# Smersh2.net
KiCad netlist of a schematic drawn in EAGLE
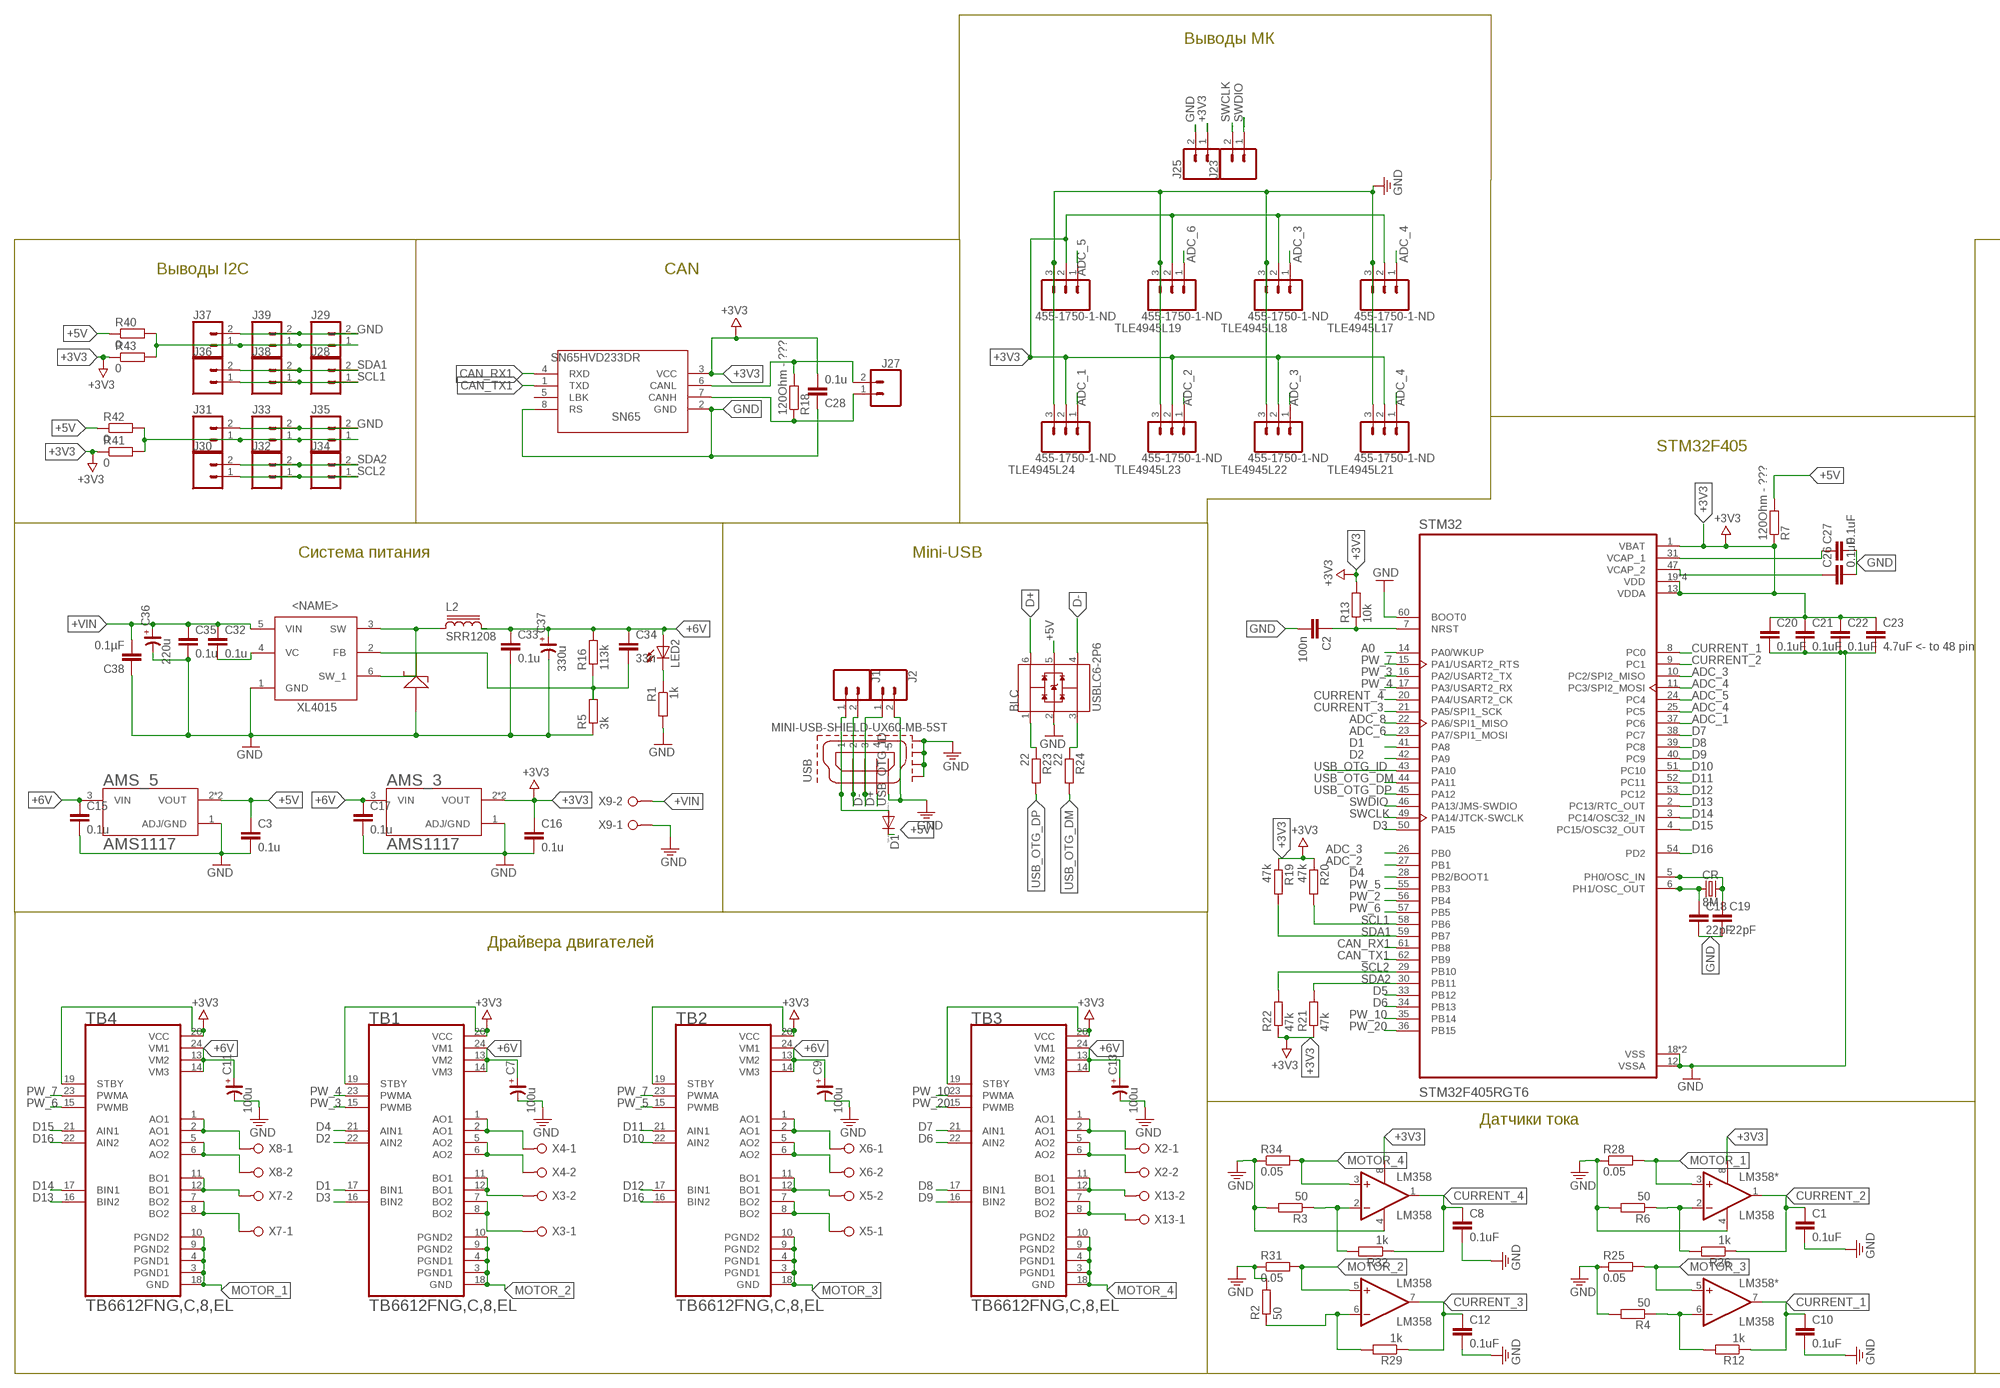
[diagram p0: schematic, sheet 1, part 1 of 2]
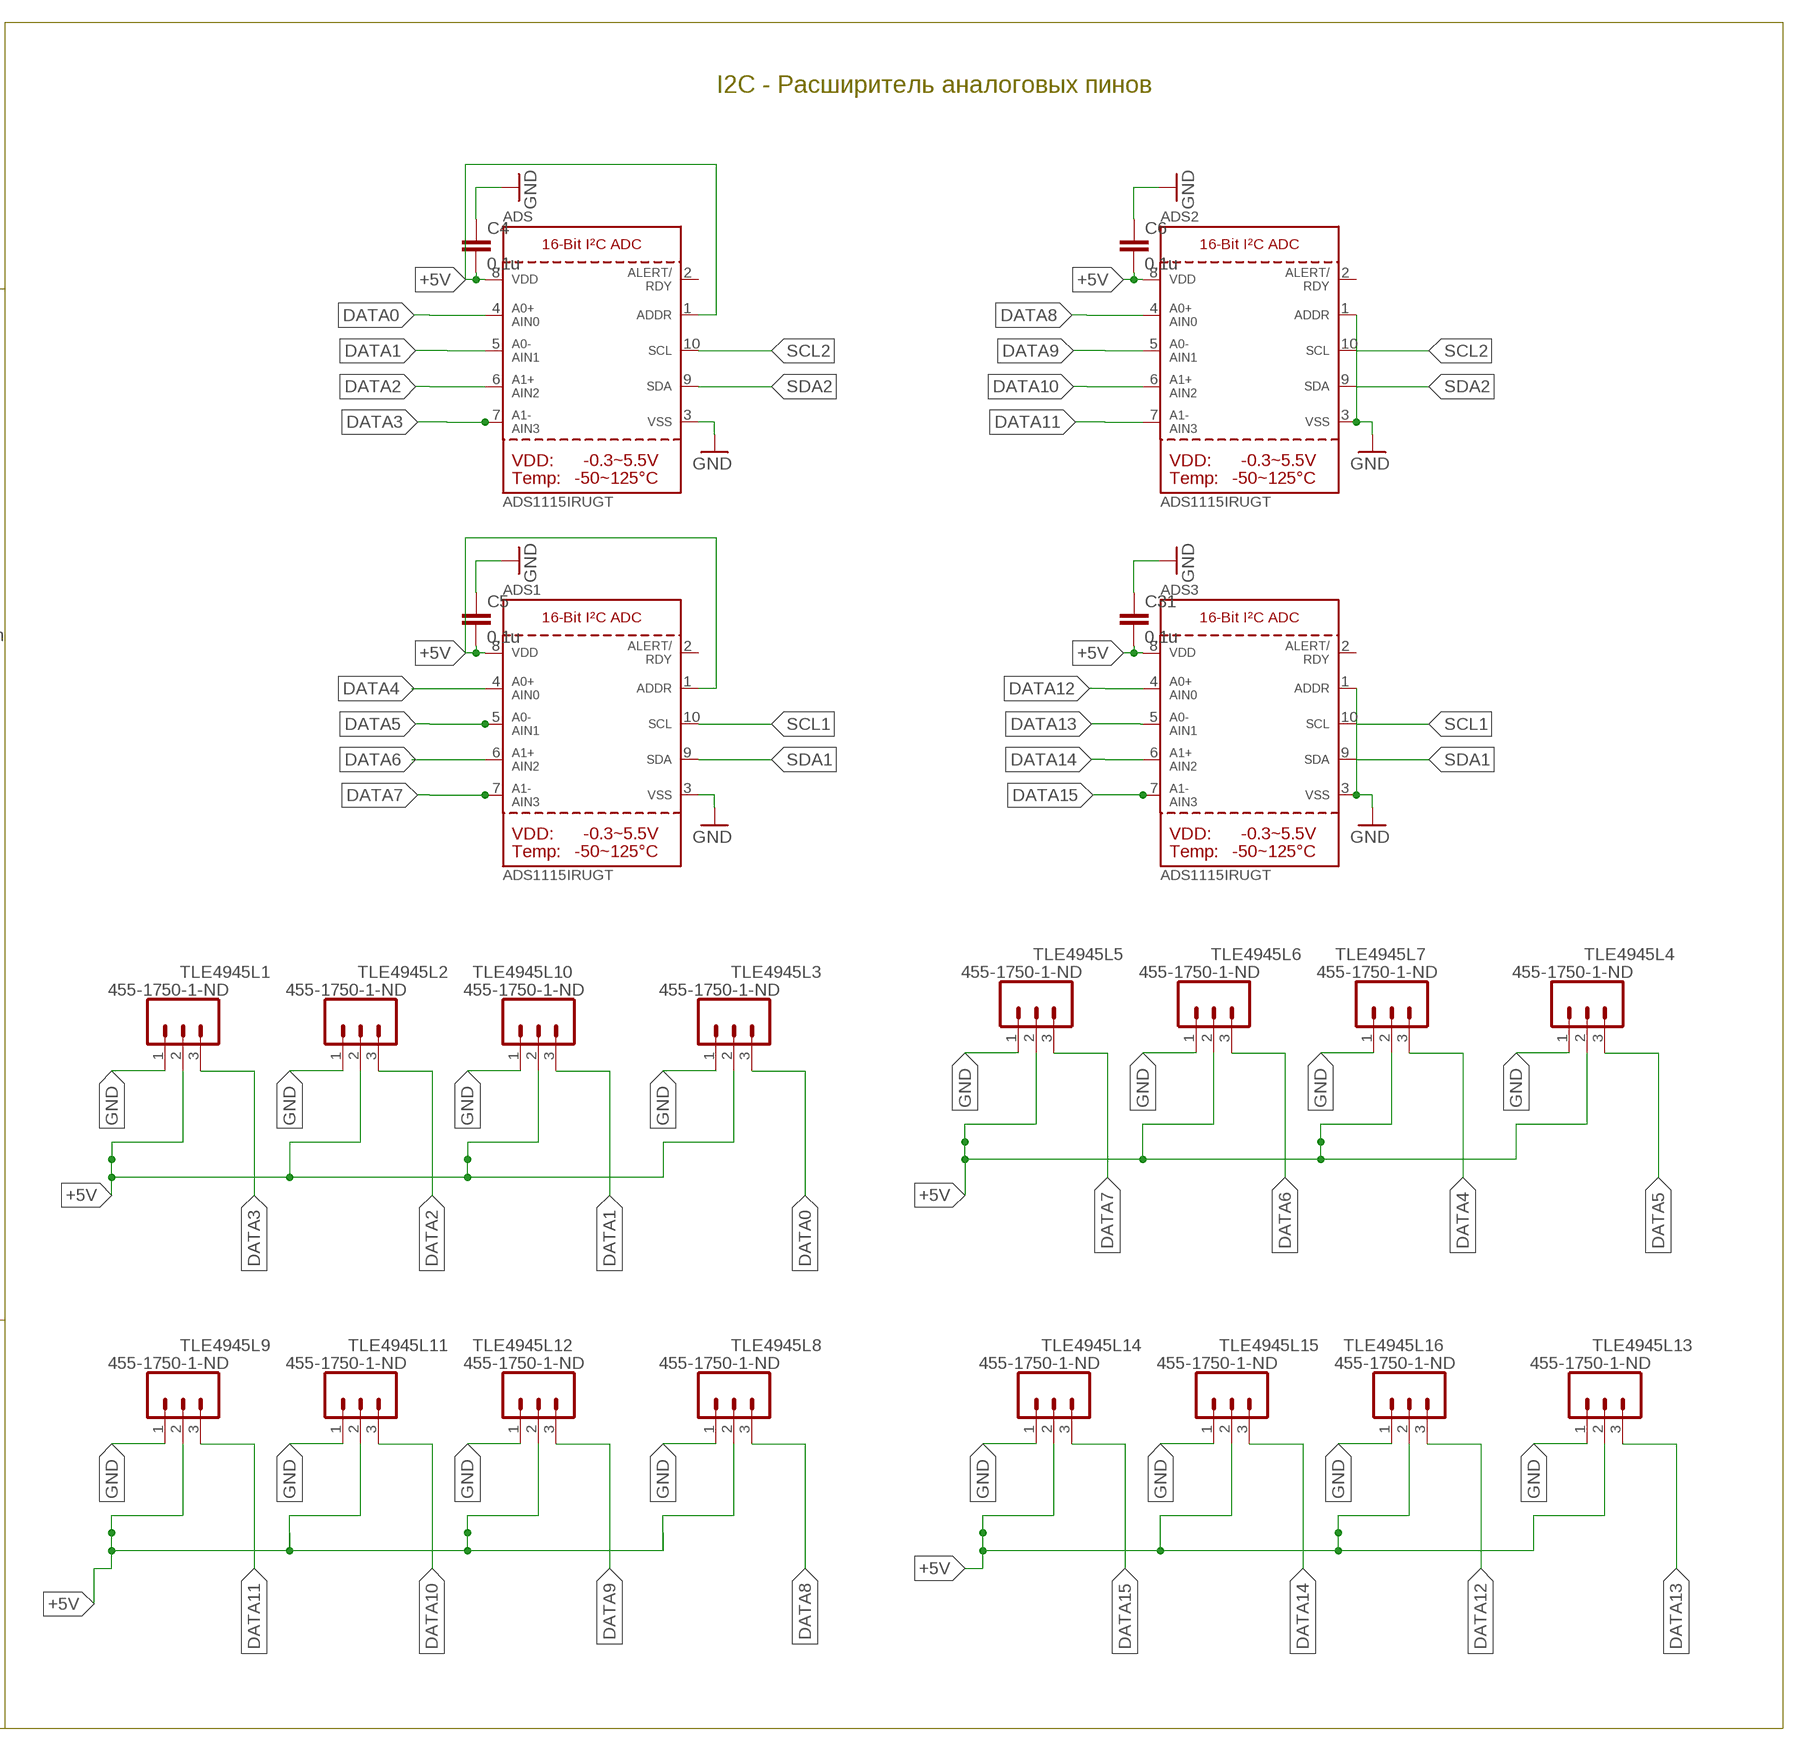
[diagram p1: schematic, sheet 1, part 2 of 2]

(export (version "E")
  (design (tool "Eeschema 10.0.6"))
  (components
    (comp (ref "ADS")
      (value "ADS1115IRUGT")
      (footprint "eagle-import:MSOP10")
      (fields (field (name "MF") "Texas Instruments"))
      (libsource (lib "eagle-import") (part "ADS1115IRUGT"))
    )
    (comp (ref "ADS1")
      (value "ADS1115IRUGT")
      (footprint "eagle-import:MSOP10")
      (fields (field (name "MF") "Texas Instruments"))
      (libsource (lib "eagle-import") (part "ADS1115IRUGT"))
    )
    (comp (ref "ADS2")
      (value "ADS1115IRUGT")
      (footprint "eagle-import:MSOP10")
      (fields (field (name "MF") "Texas Instruments"))
      (libsource (lib "eagle-import") (part "ADS1115IRUGT"))
    )
    (comp (ref "ADS3")
      (value "ADS1115IRUGT")
      (footprint "eagle-import:MSOP10")
      (fields (field (name "MF") "Texas Instruments"))
      (libsource (lib "eagle-import") (part "ADS1115IRUGT"))
    )
    (comp (ref "AMS_3")
      (value "AMS1117")
      (footprint "eagle-import:SOT229P700X180-4N")
      (fields (field (name "MF") "Seeed Technology"))
      (libsource (lib "eagle-import") (part "AMS1117"))
    )
    (comp (ref "AMS_5")
      (value "AMS1117")
      (footprint "eagle-import:SOT229P700X180-4N")
      (fields (field (name "MF") "Seeed Technology"))
      (libsource (lib "eagle-import") (part "AMS1117"))
    )
    (comp (ref "BLC")
      (value "USBLC6-2P6")
      (footprint "eagle-import:SOT50P160X60-6N")
      (fields (field (name "MF") "STMicroelectronics") (field (name "MP") "USBLC62P6"))
      (libsource (lib "eagle-import") (part "USBLC6-2P6"))
    )
    (comp (ref "C1")
      (value "0.1uF")
      (footprint "eagle-import:C0603")
      (libsource (lib "eagle-import") (part "resistor_C-EUC0603"))
    )
    (comp (ref "C2")
      (value "100n")
      (footprint "eagle-import:C0603")
      (libsource (lib "eagle-import") (part "resistor_C-EUC0603"))
    )
    (comp (ref "C3")
      (value "0.1u")
      (footprint "eagle-import:C0805")
      (libsource (lib "eagle-import") (part "resistor_C-EUC0805"))
    )
    (comp (ref "C4")
      (value "0.1u")
      (footprint "eagle-import:C0805")
      (libsource (lib "eagle-import") (part "resistor_C-EUC0805"))
    )
    (comp (ref "C5")
      (value "0.1u")
      (footprint "eagle-import:C0805")
      (libsource (lib "eagle-import") (part "resistor_C-EUC0805"))
    )
    (comp (ref "C6")
      (value "0.1u")
      (footprint "eagle-import:C0805")
      (libsource (lib "eagle-import") (part "resistor_C-EUC0805"))
    )
    (comp (ref "C7")
      (value "100u")
      (footprint "eagle-import:CSV-B")
      (libsource (lib "eagle-import") (part "CP_SV-B"))
    )
    (comp (ref "C8")
      (value "0.1uF")
      (footprint "eagle-import:C0603")
      (libsource (lib "eagle-import") (part "resistor_C-EUC0603"))
    )
    (comp (ref "C9")
      (value "100u")
      (footprint "eagle-import:CSV-B")
      (libsource (lib "eagle-import") (part "CP_SV-B"))
    )
    (comp (ref "C10")
      (value "0.1uF")
      (footprint "eagle-import:C0603")
      (libsource (lib "eagle-import") (part "resistor_C-EUC0603"))
    )
    (comp (ref "C11")
      (value "100u")
      (footprint "eagle-import:CSV-B")
      (libsource (lib "eagle-import") (part "CP_SV-B"))
    )
    (comp (ref "C12")
      (value "0.1uF")
      (footprint "eagle-import:C0603")
      (libsource (lib "eagle-import") (part "resistor_C-EUC0603"))
    )
    (comp (ref "C13")
      (value "100u")
      (footprint "eagle-import:CSV-B")
      (libsource (lib "eagle-import") (part "CP_SV-B"))
    )
    (comp (ref "C15")
      (value "0.1u")
      (footprint "eagle-import:C0805")
      (libsource (lib "eagle-import") (part "resistor_C-EUC0805"))
    )
    (comp (ref "C16")
      (value "0.1u")
      (footprint "eagle-import:C0805")
      (libsource (lib "eagle-import") (part "resistor_C-EUC0805"))
    )
    (comp (ref "C17")
      (value "0.1u")
      (footprint "eagle-import:C0805")
      (libsource (lib "eagle-import") (part "resistor_C-EUC0805"))
    )
    (comp (ref "C18")
      (value "22pF")
      (footprint "eagle-import:C0603")
      (libsource (lib "eagle-import") (part "resistor_C-EUC0603"))
    )
    (comp (ref "C19")
      (value "22pF")
      (footprint "eagle-import:C0603")
      (libsource (lib "eagle-import") (part "resistor_C-EUC0603"))
    )
    (comp (ref "C20")
      (value "0.1uF")
      (footprint "eagle-import:C0805")
      (libsource (lib "eagle-import") (part "resistor_C-EUC0805"))
    )
    (comp (ref "C21")
      (value "0.1uF")
      (footprint "eagle-import:C0603")
      (libsource (lib "eagle-import") (part "resistor_C-EUC0603"))
    )
    (comp (ref "C22")
      (value "0.1uF")
      (footprint "eagle-import:C0805")
      (libsource (lib "eagle-import") (part "resistor_C-EUC0805"))
    )
    (comp (ref "C23")
      (value "4.7uF <- to 48 pin")
      (footprint "eagle-import:C0805")
      (libsource (lib "eagle-import") (part "resistor_C-EUC0805"))
    )
    (comp (ref "C26")
      (value "0.1uF")
      (footprint "eagle-import:C0603")
      (libsource (lib "eagle-import") (part "resistor_C-EUC0603"))
    )
    (comp (ref "C27")
      (value "0.1uF")
      (footprint "eagle-import:C0603")
      (libsource (lib "eagle-import") (part "resistor_C-EUC0603"))
    )
    (comp (ref "C28")
      (value "0.1u")
      (footprint "eagle-import:C0805")
      (libsource (lib "eagle-import") (part "resistor_C-EUC0805"))
    )
    (comp (ref "C31")
      (value "0.1u")
      (footprint "eagle-import:C0805")
      (libsource (lib "eagle-import") (part "resistor_C-EUC0805"))
    )
    (comp (ref "C32")
      (value "0.1u")
      (footprint "eagle-import:C0805")
      (libsource (lib "eagle-import") (part "resistor_C-EUC0805"))
    )
    (comp (ref "C33")
      (value "0.1u")
      (footprint "eagle-import:C0805")
      (libsource (lib "eagle-import") (part "resistor_C-EUC0805"))
    )
    (comp (ref "C34")
      (value "33n")
      (footprint "eagle-import:C0805")
      (libsource (lib "eagle-import") (part "resistor_C-EUC0805"))
    )
    (comp (ref "C35")
      (value "0.1u")
      (footprint "eagle-import:C0805")
      (libsource (lib "eagle-import") (part "resistor_C-EUC0805"))
    )
    (comp (ref "C36")
      (value "220u")
      (footprint "eagle-import:CSV-D")
      (libsource (lib "eagle-import") (part "CP_SV-D"))
    )
    (comp (ref "C37")
      (value "330u")
      (footprint "eagle-import:CSV-D")
      (libsource (lib "eagle-import") (part "CP_SV-D"))
    )
    (comp (ref "C38")
      (value "0.1µF")
      (footprint "eagle-import:C0805")
      (libsource (lib "eagle-import") (part "C-EUC0805"))
    )
    (comp (ref "CR")
      (value "8M")
      (footprint "eagle-import:CRYSTAL-SMD-3.2X2.5MM")
      (libsource (lib "eagle-import") (part "CRYSTALSMD-3.2X2.5"))
    )
    (comp (ref "D1")
      (value "DIODE-MELF-MLL41")
      (footprint "eagle-import:MELF-MLL41")
      (libsource (lib "eagle-import") (part "DIODE-MELF-MLL41"))
    )
    (comp (ref "DIOD")
      (value "SK54")
      (footprint "eagle-import:DO214AA")
      (libsource (lib "eagle-import") (part "SK54"))
    )
    (comp (ref "J1")
      (value "CONN_02")
      (footprint "eagle-import:1X02")
      (libsource (lib "eagle-import") (part "CONN_02"))
    )
    (comp (ref "J2")
      (value "CONN_02")
      (footprint "eagle-import:1X02")
      (libsource (lib "eagle-import") (part "CONN_02"))
    )
    (comp (ref "J23")
      (value "CONN_02")
      (footprint "eagle-import:1X02")
      (libsource (lib "eagle-import") (part "CONN_02"))
    )
    (comp (ref "J25")
      (value "CONN_02")
      (footprint "eagle-import:1X02")
      (libsource (lib "eagle-import") (part "CONN_02"))
    )
    (comp (ref "J27")
      (value "CONN_02")
      (footprint "eagle-import:1X02")
      (libsource (lib "eagle-import") (part "CONN_02"))
    )
    (comp (ref "J28")
      (value "CONN_02")
      (footprint "eagle-import:1X02")
      (libsource (lib "eagle-import") (part "CONN_02"))
    )
    (comp (ref "J29")
      (value "CONN_02")
      (footprint "eagle-import:1X02")
      (libsource (lib "eagle-import") (part "CONN_02"))
    )
    (comp (ref "J30")
      (value "CONN_02")
      (footprint "eagle-import:1X02")
      (libsource (lib "eagle-import") (part "CONN_02"))
    )
    (comp (ref "J31")
      (value "CONN_02")
      (footprint "eagle-import:1X02")
      (libsource (lib "eagle-import") (part "CONN_02"))
    )
    (comp (ref "J32")
      (value "CONN_02")
      (footprint "eagle-import:1X02")
      (libsource (lib "eagle-import") (part "CONN_02"))
    )
    (comp (ref "J33")
      (value "CONN_02")
      (footprint "eagle-import:1X02")
      (libsource (lib "eagle-import") (part "CONN_02"))
    )
    (comp (ref "J34")
      (value "CONN_02")
      (footprint "eagle-import:1X02")
      (libsource (lib "eagle-import") (part "CONN_02"))
    )
    (comp (ref "J35")
      (value "CONN_02")
      (footprint "eagle-import:1X02")
      (libsource (lib "eagle-import") (part "CONN_02"))
    )
    (comp (ref "J36")
      (value "CONN_02")
      (footprint "eagle-import:1X02")
      (libsource (lib "eagle-import") (part "CONN_02"))
    )
    (comp (ref "J37")
      (value "CONN_02")
      (footprint "eagle-import:1X02")
      (libsource (lib "eagle-import") (part "CONN_02"))
    )
    (comp (ref "J38")
      (value "CONN_02")
      (footprint "eagle-import:1X02")
      (libsource (lib "eagle-import") (part "CONN_02"))
    )
    (comp (ref "J39")
      (value "CONN_02")
      (footprint "eagle-import:1X02")
      (libsource (lib "eagle-import") (part "CONN_02"))
    )
    (comp (ref "L2")
      (value "SRR1208")
      (footprint "eagle-import:SSR1208")
      (libsource (lib "eagle-import") (part "SRR1208"))
    )
    (comp (ref "LED2")
      (value "LEDCHIPLED_0805")
      (footprint "eagle-import:CHIPLED_0805")
      (libsource (lib "eagle-import") (part "LEDCHIPLED_0805"))
    )
    (comp (ref "LM358")
      (value "LM358")
      (footprint "eagle-import:LM358")
      (libsource (lib "eagle-import") (part "LM358"))
    )
    (comp (ref "LM358*")
      (value "LM358")
      (footprint "eagle-import:LM358")
      (libsource (lib "eagle-import") (part "LM358"))
    )
    (comp (ref "R1")
      (value "1k")
      (footprint "eagle-import:R0805")
      (libsource (lib "eagle-import") (part "R-EU_R0805"))
    )
    (comp (ref "R2")
      (value "50")
      (footprint "eagle-import:R0603")
      (libsource (lib "eagle-import") (part "resistor_R-EU_R0603"))
    )
    (comp (ref "R3")
      (value "50")
      (footprint "eagle-import:R0603")
      (libsource (lib "eagle-import") (part "resistor_R-EU_R0603"))
    )
    (comp (ref "R4")
      (value "50")
      (footprint "eagle-import:R1206")
      (libsource (lib "eagle-import") (part "resistor_R-EU_R1206"))
    )
    (comp (ref "R5")
      (value "3k")
      (footprint "eagle-import:M0805")
      (libsource (lib "eagle-import") (part "rcl@1_R-EU_M0805"))
    )
    (comp (ref "R6")
      (value "50")
      (footprint "eagle-import:R0603")
      (libsource (lib "eagle-import") (part "resistor_R-EU_R0603"))
    )
    (comp (ref "R7")
      (value "120Ohm - ???")
      (footprint "eagle-import:R0805")
      (libsource (lib "eagle-import") (part "resistor_R-EU_R0805"))
    )
    (comp (ref "R12")
      (value "1k")
      (footprint "eagle-import:R0603")
      (libsource (lib "eagle-import") (part "resistor_R-EU_R0603"))
    )
    (comp (ref "R13")
      (value "10k")
      (footprint "eagle-import:R0603")
      (libsource (lib "eagle-import") (part "resistor_R-EU_R0603"))
    )
    (comp (ref "R16")
      (value "113k")
      (footprint "eagle-import:M0805")
      (libsource (lib "eagle-import") (part "rcl@1_R-EU_M0805"))
    )
    (comp (ref "R18")
      (value "120Ohm - ???")
      (footprint "eagle-import:R0805")
      (libsource (lib "eagle-import") (part "resistor_R-EU_R0805"))
    )
    (comp (ref "R19")
      (value "47k")
      (footprint "eagle-import:R0805")
      (libsource (lib "eagle-import") (part "resistor_R-EU_R0805"))
    )
    (comp (ref "R20")
      (value "47k")
      (footprint "eagle-import:R0805")
      (libsource (lib "eagle-import") (part "resistor_R-EU_R0805"))
    )
    (comp (ref "R21")
      (value "47k")
      (footprint "eagle-import:R0805")
      (libsource (lib "eagle-import") (part "resistor_R-EU_R0805"))
    )
    (comp (ref "R22")
      (value "47k")
      (footprint "eagle-import:R0805")
      (libsource (lib "eagle-import") (part "resistor_R-EU_R0805"))
    )
    (comp (ref "R23")
      (value "22")
      (footprint "eagle-import:R0805")
      (libsource (lib "eagle-import") (part "resistor_R-EU_R0805"))
    )
    (comp (ref "R24")
      (value "22")
      (footprint "eagle-import:R0805")
      (libsource (lib "eagle-import") (part "resistor_R-EU_R0805"))
    )
    (comp (ref "R25")
      (value "0.05")
      (footprint "eagle-import:R1206")
      (libsource (lib "eagle-import") (part "resistor_R-EU_R1206"))
    )
    (comp (ref "R26")
      (value "1k")
      (footprint "eagle-import:R0603")
      (libsource (lib "eagle-import") (part "resistor_R-EU_R0603"))
    )
    (comp (ref "R28")
      (value "0.05")
      (footprint "eagle-import:R1206")
      (libsource (lib "eagle-import") (part "resistor_R-EU_R1206"))
    )
    (comp (ref "R29")
      (value "1k")
      (footprint "eagle-import:R0603")
      (libsource (lib "eagle-import") (part "resistor_R-EU_R0603"))
    )
    (comp (ref "R31")
      (value "0.05")
      (footprint "eagle-import:R1206")
      (libsource (lib "eagle-import") (part "resistor_R-EU_R1206"))
    )
    (comp (ref "R32")
      (value "1k")
      (footprint "eagle-import:R0603")
      (libsource (lib "eagle-import") (part "resistor_R-EU_R0603"))
    )
    (comp (ref "R34")
      (value "0.05")
      (footprint "eagle-import:R1206")
      (libsource (lib "eagle-import") (part "resistor_R-EU_R1206"))
    )
    (comp (ref "R40")
      (value "0")
      (footprint "eagle-import:R0805")
      (libsource (lib "eagle-import") (part "resistor_R-EU_R0805"))
    )
    (comp (ref "R41")
      (value "0")
      (footprint "eagle-import:R0805")
      (libsource (lib "eagle-import") (part "resistor_R-EU_R0805"))
    )
    (comp (ref "R42")
      (value "0")
      (footprint "eagle-import:R0805")
      (libsource (lib "eagle-import") (part "resistor_R-EU_R0805"))
    )
    (comp (ref "R43")
      (value "0")
      (footprint "eagle-import:R0805")
      (libsource (lib "eagle-import") (part "resistor_R-EU_R0805"))
    )
    (comp (ref "SN65")
      (value "SN65HVD233DR")
      (footprint "eagle-import:SOIC8")
      (fields (field (name "MF") "Texas Instruments"))
      (libsource (lib "eagle-import") (part "SN65HVD233DR"))
    )
    (comp (ref "STM32")
      (value "STM32F405RGT6")
      (footprint "eagle-import:QFP50P1200X1200X160-64N")
      (fields (field (name "MF") "STMicroelectronics"))
      (libsource (lib "eagle-import") (part "STM32F405RGT6"))
    )
    (comp (ref "TB1")
      (value "TB6612FNG,C,8,EL")
      (footprint "eagle-import:SOP65P760X160-24N")
      (fields (field (name "MF") "Toshiba"))
      (libsource (lib "eagle-import") (part "TB6612FNG,C,8,EL"))
    )
    (comp (ref "TB2")
      (value "TB6612FNG,C,8,EL")
      (footprint "eagle-import:SOP65P760X160-24N")
      (fields (field (name "MF") "Toshiba"))
      (libsource (lib "eagle-import") (part "TB6612FNG,C,8,EL"))
    )
    (comp (ref "TB3")
      (value "TB6612FNG,C,8,EL")
      (footprint "eagle-import:SOP65P760X160-24N")
      (fields (field (name "MF") "Toshiba"))
      (libsource (lib "eagle-import") (part "TB6612FNG,C,8,EL"))
    )
    (comp (ref "TB4")
      (value "TB6612FNG,C,8,EL")
      (footprint "eagle-import:SOP65P760X160-24N")
      (fields (field (name "MF") "Toshiba"))
      (libsource (lib "eagle-import") (part "TB6612FNG,C,8,EL"))
    )
    (comp (ref "TLE4945L1")
      (value "455-1750-1-ND")
      (footprint "eagle-import:1X03")
      (libsource (lib "eagle-import") (part "CONN_03"))
    )
    (comp (ref "TLE4945L2")
      (value "455-1750-1-ND")
      (footprint "eagle-import:1X03")
      (libsource (lib "eagle-import") (part "CONN_03"))
    )
    (comp (ref "TLE4945L3")
      (value "455-1750-1-ND")
      (footprint "eagle-import:1X03")
      (libsource (lib "eagle-import") (part "CONN_03"))
    )
    (comp (ref "TLE4945L4")
      (value "455-1750-1-ND")
      (footprint "eagle-import:1X03")
      (libsource (lib "eagle-import") (part "CONN_03"))
    )
    (comp (ref "TLE4945L5")
      (value "455-1750-1-ND")
      (footprint "eagle-import:1X03")
      (libsource (lib "eagle-import") (part "CONN_03"))
    )
    (comp (ref "TLE4945L6")
      (value "455-1750-1-ND")
      (footprint "eagle-import:1X03")
      (libsource (lib "eagle-import") (part "CONN_03"))
    )
    (comp (ref "TLE4945L7")
      (value "455-1750-1-ND")
      (footprint "eagle-import:1X03")
      (libsource (lib "eagle-import") (part "CONN_03"))
    )
    (comp (ref "TLE4945L8")
      (value "455-1750-1-ND")
      (footprint "eagle-import:1X03")
      (libsource (lib "eagle-import") (part "CONN_03"))
    )
    (comp (ref "TLE4945L9")
      (value "455-1750-1-ND")
      (footprint "eagle-import:1X03")
      (libsource (lib "eagle-import") (part "CONN_03"))
    )
    (comp (ref "TLE4945L10")
      (value "455-1750-1-ND")
      (footprint "eagle-import:1X03")
      (libsource (lib "eagle-import") (part "CONN_03"))
    )
    (comp (ref "TLE4945L11")
      (value "455-1750-1-ND")
      (footprint "eagle-import:1X03")
      (libsource (lib "eagle-import") (part "CONN_03"))
    )
    (comp (ref "TLE4945L12")
      (value "455-1750-1-ND")
      (footprint "eagle-import:1X03")
      (libsource (lib "eagle-import") (part "CONN_03"))
    )
    (comp (ref "TLE4945L13")
      (value "455-1750-1-ND")
      (footprint "eagle-import:1X03")
      (libsource (lib "eagle-import") (part "CONN_03"))
    )
    (comp (ref "TLE4945L14")
      (value "455-1750-1-ND")
      (footprint "eagle-import:1X03")
      (libsource (lib "eagle-import") (part "CONN_03"))
    )
    (comp (ref "TLE4945L15")
      (value "455-1750-1-ND")
      (footprint "eagle-import:1X03")
      (libsource (lib "eagle-import") (part "CONN_03"))
    )
    (comp (ref "TLE4945L16")
      (value "455-1750-1-ND")
      (footprint "eagle-import:1X03")
      (libsource (lib "eagle-import") (part "CONN_03"))
    )
    (comp (ref "TLE4945L17")
      (value "455-1750-1-ND")
      (footprint "eagle-import:1X03")
      (libsource (lib "eagle-import") (part "CONN_03"))
    )
    (comp (ref "TLE4945L18")
      (value "455-1750-1-ND")
      (footprint "eagle-import:1X03")
      (libsource (lib "eagle-import") (part "CONN_03"))
    )
    (comp (ref "TLE4945L19")
      (value "455-1750-1-ND")
      (footprint "eagle-import:1X03")
      (libsource (lib "eagle-import") (part "CONN_03"))
    )
    (comp (ref "TLE4945L20")
      (value "455-1750-1-ND")
      (footprint "eagle-import:1X03")
      (libsource (lib "eagle-import") (part "CONN_03"))
    )
    (comp (ref "TLE4945L21")
      (value "455-1750-1-ND")
      (footprint "eagle-import:1X03")
      (libsource (lib "eagle-import") (part "CONN_03"))
    )
    (comp (ref "TLE4945L22")
      (value "455-1750-1-ND")
      (footprint "eagle-import:1X03")
      (libsource (lib "eagle-import") (part "CONN_03"))
    )
    (comp (ref "TLE4945L23")
      (value "455-1750-1-ND")
      (footprint "eagle-import:1X03")
      (libsource (lib "eagle-import") (part "CONN_03"))
    )
    (comp (ref "TLE4945L24")
      (value "455-1750-1-ND")
      (footprint "eagle-import:1X03")
      (libsource (lib "eagle-import") (part "CONN_03"))
    )
    (comp (ref "USB")
      (value "MINI-USB-SHIELD-UX60-MB-5ST")
      (footprint "eagle-import:UX60-MB-5ST")
      (libsource (lib "eagle-import") (part "MINI-USB-SHIELD-UX60-MB-5ST"))
    )
    (comp (ref "X2")
      (value "W237-02P")
      (footprint "eagle-import:W237-132")
      (libsource (lib "eagle-import") (part "W237-02P"))
    )
    (comp (ref "X3")
      (value "W237-02P")
      (footprint "eagle-import:W237-132")
      (libsource (lib "eagle-import") (part "W237-02P"))
    )
    (comp (ref "X4")
      (value "W237-02P")
      (footprint "eagle-import:W237-132")
      (libsource (lib "eagle-import") (part "W237-02P"))
    )
    (comp (ref "X5")
      (value "W237-02P")
      (footprint "eagle-import:W237-132")
      (libsource (lib "eagle-import") (part "W237-02P"))
    )
    (comp (ref "X6")
      (value "W237-02P")
      (footprint "eagle-import:W237-132")
      (libsource (lib "eagle-import") (part "W237-02P"))
    )
    (comp (ref "X7")
      (value "W237-02P")
      (footprint "eagle-import:W237-132")
      (libsource (lib "eagle-import") (part "W237-02P"))
    )
    (comp (ref "X8")
      (value "W237-02P")
      (footprint "eagle-import:W237-132")
      (libsource (lib "eagle-import") (part "W237-02P"))
    )
    (comp (ref "X9")
      (value "W237-02P")
      (footprint "eagle-import:W237-132")
      (libsource (lib "eagle-import") (part "W237-02P"))
    )
    (comp (ref "X13")
      (value "W237-02P")
      (footprint "eagle-import:W237-132")
      (libsource (lib "eagle-import") (part "W237-02P"))
    )
    (comp (ref "XL4015")
      (value "XL4015")
      (footprint "eagle-import:TO263-5L")
      (libsource (lib "eagle-import") (part "XL4015"))
    )
  )
  (nets
    (net (code "1") (name "+3V3") (class "Default")
      (node (ref "AMS_3") (pin "2") (pinfunction "VOUT_2") (pintype "output"))
      (node (ref "AMS_3") (pin "4") (pinfunction "VOUT_4") (pintype "output"))
      (node (ref "C16") (pin "1") (pinfunction "1_1") (pintype "passive"))
      (node (ref "C20") (pin "1") (pinfunction "1_1") (pintype "passive"))
      (node (ref "C21") (pin "1") (pinfunction "1_1") (pintype "passive"))
      (node (ref "C22") (pin "1") (pinfunction "1_1") (pintype "passive"))
      (node (ref "C23") (pin "1") (pinfunction "1_1") (pintype "passive"))
      (node (ref "C28") (pin "2") (pinfunction "2_2") (pintype "passive"))
      (node (ref "J25") (pin "1") (pinfunction "1_1") (pintype "passive"))
      (node (ref "LM358") (pin "8") (pinfunction "V+_8") (pintype "power_in"))
      (node (ref "LM358*") (pin "8") (pinfunction "V+_8") (pintype "power_in"))
      (node (ref "R13") (pin "2") (pinfunction "2_2") (pintype "passive"))
      (node (ref "R19") (pin "1") (pinfunction "1_1") (pintype "passive"))
      (node (ref "R20") (pin "1") (pinfunction "1_1") (pintype "passive"))
      (node (ref "R21") (pin "1") (pinfunction "1_1") (pintype "passive"))
      (node (ref "R22") (pin "1") (pinfunction "1_1") (pintype "passive"))
      (node (ref "R41") (pin "1") (pinfunction "1_1") (pintype "passive"))
      (node (ref "R43") (pin "1") (pinfunction "1_1") (pintype "passive"))
      (node (ref "R7") (pin "1") (pinfunction "1_1") (pintype "passive"))
      (node (ref "SN65") (pin "3") (pinfunction "VCC_3") (pintype "power_in"))
      (node (ref "STM32") (pin "1") (pinfunction "VBAT_1") (pintype "power_in"))
      (node (ref "STM32") (pin "13") (pinfunction "VDDA_13") (pintype "power_in"))
      (node (ref "STM32") (pin "19") (pinfunction "VDD_19") (pintype "power_in"))
      (node (ref "STM32") (pin "32") (pinfunction "VDD_32") (pintype "power_in"))
      (node (ref "STM32") (pin "48") (pinfunction "VDD_48") (pintype "power_in"))
      (node (ref "STM32") (pin "64") (pinfunction "VDD_64") (pintype "power_in"))
      (node (ref "TB1") (pin "19") (pinfunction "STBY_19") (pintype "input"))
      (node (ref "TB1") (pin "20") (pinfunction "VCC_20") (pintype "power_in"))
      (node (ref "TB2") (pin "19") (pinfunction "STBY_19") (pintype "input"))
      (node (ref "TB2") (pin "20") (pinfunction "VCC_20") (pintype "power_in"))
      (node (ref "TB3") (pin "19") (pinfunction "STBY_19") (pintype "input"))
      (node (ref "TB3") (pin "20") (pinfunction "VCC_20") (pintype "power_in"))
      (node (ref "TB4") (pin "19") (pinfunction "STBY_19") (pintype "input"))
      (node (ref "TB4") (pin "20") (pinfunction "VCC_20") (pintype "power_in"))
      (node (ref "TLE4945L17") (pin "2") (pinfunction "2_2") (pintype "passive"))
      (node (ref "TLE4945L18") (pin "2") (pinfunction "2_2") (pintype "passive"))
      (node (ref "TLE4945L19") (pin "2") (pinfunction "2_2") (pintype "passive"))
      (node (ref "TLE4945L20") (pin "2") (pinfunction "2_2") (pintype "passive"))
      (node (ref "TLE4945L21") (pin "2") (pinfunction "2_2") (pintype "passive"))
      (node (ref "TLE4945L22") (pin "2") (pinfunction "2_2") (pintype "passive"))
      (node (ref "TLE4945L23") (pin "2") (pinfunction "2_2") (pintype "passive"))
      (node (ref "TLE4945L24") (pin "2") (pinfunction "2_2") (pintype "passive"))
    )
    (net (code "2") (name "+5V") (class "Default")
      (node (ref "ADS") (pin "1") (pinfunction "ADDR_1") (pintype "bidirectional"))
      (node (ref "ADS") (pin "8") (pinfunction "VDD_8") (pintype "bidirectional"))
      (node (ref "ADS1") (pin "1") (pinfunction "ADDR_1") (pintype "bidirectional"))
      (node (ref "ADS1") (pin "8") (pinfunction "VDD_8") (pintype "bidirectional"))
      (node (ref "ADS2") (pin "8") (pinfunction "VDD_8") (pintype "bidirectional"))
      (node (ref "ADS3") (pin "8") (pinfunction "VDD_8") (pintype "bidirectional"))
      (node (ref "AMS_5") (pin "2") (pinfunction "VOUT_2") (pintype "output"))
      (node (ref "AMS_5") (pin "4") (pinfunction "VOUT_4") (pintype "output"))
      (node (ref "BLC") (pin "5") (pinfunction "VBUS_5") (pintype "power_in"))
      (node (ref "C3") (pin "1") (pinfunction "1_1") (pintype "passive"))
      (node (ref "C31") (pin "2") (pinfunction "2_2") (pintype "passive"))
      (node (ref "C4") (pin "2") (pinfunction "2_2") (pintype "passive"))
      (node (ref "C5") (pin "2") (pinfunction "2_2") (pintype "passive"))
      (node (ref "C6") (pin "2") (pinfunction "2_2") (pintype "passive"))
      (node (ref "D1") (pin "C") (pinfunction "C_C") (pintype "passive"))
      (node (ref "R40") (pin "1") (pinfunction "1_1") (pintype "passive"))
      (node (ref "R42") (pin "1") (pinfunction "1_1") (pintype "passive"))
      (node (ref "R7") (pin "2") (pinfunction "2_2") (pintype "passive"))
      (node (ref "TLE4945L1") (pin "2") (pinfunction "2_2") (pintype "passive"))
      (node (ref "TLE4945L10") (pin "2") (pinfunction "2_2") (pintype "passive"))
      (node (ref "TLE4945L11") (pin "2") (pinfunction "2_2") (pintype "passive"))
      (node (ref "TLE4945L12") (pin "2") (pinfunction "2_2") (pintype "passive"))
      (node (ref "TLE4945L13") (pin "2") (pinfunction "2_2") (pintype "passive"))
      (node (ref "TLE4945L14") (pin "2") (pinfunction "2_2") (pintype "passive"))
      (node (ref "TLE4945L15") (pin "2") (pinfunction "2_2") (pintype "passive"))
      (node (ref "TLE4945L16") (pin "2") (pinfunction "2_2") (pintype "passive"))
      (node (ref "TLE4945L2") (pin "2") (pinfunction "2_2") (pintype "passive"))
      (node (ref "TLE4945L3") (pin "2") (pinfunction "2_2") (pintype "passive"))
      (node (ref "TLE4945L4") (pin "2") (pinfunction "2_2") (pintype "passive"))
      (node (ref "TLE4945L5") (pin "2") (pinfunction "2_2") (pintype "passive"))
      (node (ref "TLE4945L6") (pin "2") (pinfunction "2_2") (pintype "passive"))
      (node (ref "TLE4945L7") (pin "2") (pinfunction "2_2") (pintype "passive"))
      (node (ref "TLE4945L8") (pin "2") (pinfunction "2_2") (pintype "passive"))
      (node (ref "TLE4945L9") (pin "2") (pinfunction "2_2") (pintype "passive"))
    )
    (net (code "3") (name "+6V") (class "Default")
      (node (ref "AMS_3") (pin "3") (pinfunction "VIN_3") (pintype "input"))
      (node (ref "AMS_5") (pin "3") (pinfunction "VIN_3") (pintype "input"))
      (node (ref "C11") (pin "+") (pinfunction "+_+") (pintype "passive"))
      (node (ref "C13") (pin "+") (pinfunction "+_+") (pintype "passive"))
      (node (ref "C15") (pin "1") (pinfunction "1_1") (pintype "passive"))
      (node (ref "C17") (pin "1") (pinfunction "1_1") (pintype "passive"))
      (node (ref "C33") (pin "1") (pinfunction "1_1") (pintype "passive"))
      (node (ref "C34") (pin "1") (pinfunction "1_1") (pintype "passive"))
      (node (ref "C37") (pin "+") (pinfunction "+_+") (pintype "passive"))
      (node (ref "C7") (pin "+") (pinfunction "+_+") (pintype "passive"))
      (node (ref "C9") (pin "+") (pinfunction "+_+") (pintype "passive"))
      (node (ref "L2") (pin "2") (pinfunction "2_2") (pintype "passive"))
      (node (ref "LED2") (pin "A") (pinfunction "A_A") (pintype "passive"))
      (node (ref "R16") (pin "2") (pinfunction "2_2") (pintype "passive"))
      (node (ref "TB1") (pin "13") (pinfunction "VM2_13") (pintype "power_in"))
      (node (ref "TB1") (pin "14") (pinfunction "VM3_14") (pintype "power_in"))
      (node (ref "TB1") (pin "24") (pinfunction "VM1_24") (pintype "power_in"))
      (node (ref "TB2") (pin "13") (pinfunction "VM2_13") (pintype "power_in"))
      (node (ref "TB2") (pin "14") (pinfunction "VM3_14") (pintype "power_in"))
      (node (ref "TB2") (pin "24") (pinfunction "VM1_24") (pintype "power_in"))
      (node (ref "TB3") (pin "13") (pinfunction "VM2_13") (pintype "power_in"))
      (node (ref "TB3") (pin "14") (pinfunction "VM3_14") (pintype "power_in"))
      (node (ref "TB3") (pin "24") (pinfunction "VM1_24") (pintype "power_in"))
      (node (ref "TB4") (pin "13") (pinfunction "VM2_13") (pintype "power_in"))
      (node (ref "TB4") (pin "14") (pinfunction "VM3_14") (pintype "power_in"))
      (node (ref "TB4") (pin "24") (pinfunction "VM1_24") (pintype "power_in"))
    )
    (net (code "4") (name "+VIN") (class "Default")
      (node (ref "C32") (pin "1") (pinfunction "1_1") (pintype "passive"))
      (node (ref "C35") (pin "1") (pinfunction "1_1") (pintype "passive"))
      (node (ref "C36") (pin "+") (pinfunction "+_+") (pintype "passive"))
      (node (ref "C38") (pin "2") (pinfunction "2_2") (pintype "passive"))
      (node (ref "X9") (pin "2") (pinfunction "KL_2") (pintype "passive"))
      (node (ref "XL4015") (pin "5") (pinfunction "VIN_5") (pintype "bidirectional"))
    )
    (net (code "5") (name "/A0") (class "Default")
      (node (ref "STM32") (pin "14") (pinfunction "PA0/WKUP_14") (pintype "bidirectional"))
    )
    (net (code "6") (name "/ADC_1") (class "Default")
      (node (ref "STM32") (pin "37") (pinfunction "PC6_37") (pintype "bidirectional"))
      (node (ref "TLE4945L24") (pin "1") (pinfunction "1_1") (pintype "passive"))
    )
    (net (code "7") (name "/ADC_2") (class "Default")
      (node (ref "STM32") (pin "27") (pinfunction "PB1_27") (pintype "bidirectional"))
      (node (ref "TLE4945L23") (pin "1") (pinfunction "1_1") (pintype "passive"))
    )
    (net (code "8") (name "/ADC_3") (class "Default")
      (node (ref "STM32") (pin "10") (pinfunction "PC2/SPI2_MISO_10") (pintype "bidirectional"))
      (node (ref "STM32") (pin "26") (pinfunction "PB0_26") (pintype "bidirectional"))
      (node (ref "TLE4945L18") (pin "1") (pinfunction "1_1") (pintype "passive"))
      (node (ref "TLE4945L22") (pin "1") (pinfunction "1_1") (pintype "passive"))
    )
    (net (code "9") (name "/ADC_4") (class "Default")
      (node (ref "STM32") (pin "11") (pinfunction "PC3/SPI2_MOSI_11") (pintype "bidirectional"))
      (node (ref "STM32") (pin "25") (pinfunction "PC5_25") (pintype "bidirectional"))
      (node (ref "TLE4945L17") (pin "1") (pinfunction "1_1") (pintype "passive"))
      (node (ref "TLE4945L21") (pin "1") (pinfunction "1_1") (pintype "passive"))
    )
    (net (code "10") (name "/ADC_5") (class "Default")
      (node (ref "STM32") (pin "24") (pinfunction "PC4_24") (pintype "bidirectional"))
      (node (ref "TLE4945L20") (pin "1") (pinfunction "1_1") (pintype "passive"))
    )
    (net (code "11") (name "/ADC_6") (class "Default")
      (node (ref "STM32") (pin "23") (pinfunction "PA7/SPI1_MOSI_23") (pintype "bidirectional"))
      (node (ref "TLE4945L19") (pin "1") (pinfunction "1_1") (pintype "passive"))
    )
    (net (code "12") (name "/ADC_8") (class "Default")
      (node (ref "STM32") (pin "22") (pinfunction "PA6/SPI1_MISO_22") (pintype "bidirectional"))
    )
    (net (code "13") (name "/D1") (class "Default")
      (node (ref "STM32") (pin "41") (pinfunction "PA8_41") (pintype "bidirectional"))
      (node (ref "TB1") (pin "17") (pinfunction "BIN1_17") (pintype "input"))
    )
    (net (code "14") (name "/D2") (class "Default")
      (node (ref "STM32") (pin "42") (pinfunction "PA9_42") (pintype "bidirectional"))
      (node (ref "TB1") (pin "22") (pinfunction "AIN2_22") (pintype "input"))
    )
    (net (code "15") (name "/D3") (class "Default")
      (node (ref "STM32") (pin "50") (pinfunction "PA15_50") (pintype "bidirectional"))
      (node (ref "TB1") (pin "16") (pinfunction "BIN2_16") (pintype "input"))
    )
    (net (code "16") (name "/D4") (class "Default")
      (node (ref "STM32") (pin "28") (pinfunction "PB2/BOOT1_28") (pintype "bidirectional"))
      (node (ref "TB1") (pin "21") (pinfunction "AIN1_21") (pintype "input"))
    )
    (net (code "17") (name "/D5") (class "Default")
      (node (ref "STM32") (pin "33") (pinfunction "PB12_33") (pintype "bidirectional"))
    )
    (net (code "18") (name "/D6") (class "Default")
      (node (ref "STM32") (pin "34") (pinfunction "PB13_34") (pintype "bidirectional"))
      (node (ref "TB3") (pin "22") (pinfunction "AIN2_22") (pintype "input"))
    )
    (net (code "19") (name "/D7") (class "Default")
      (node (ref "STM32") (pin "38") (pinfunction "PC7_38") (pintype "bidirectional"))
      (node (ref "TB3") (pin "21") (pinfunction "AIN1_21") (pintype "input"))
    )
    (net (code "20") (name "/D8") (class "Default")
      (node (ref "STM32") (pin "39") (pinfunction "PC8_39") (pintype "bidirectional"))
      (node (ref "TB3") (pin "17") (pinfunction "BIN1_17") (pintype "input"))
    )
    (net (code "21") (name "/D9") (class "Default")
      (node (ref "STM32") (pin "40") (pinfunction "PC9_40") (pintype "bidirectional"))
      (node (ref "TB3") (pin "16") (pinfunction "BIN2_16") (pintype "input"))
    )
    (net (code "22") (name "/D10") (class "Default")
      (node (ref "STM32") (pin "51") (pinfunction "PC10_51") (pintype "bidirectional"))
      (node (ref "TB2") (pin "22") (pinfunction "AIN2_22") (pintype "input"))
    )
    (net (code "23") (name "/D11") (class "Default")
      (node (ref "STM32") (pin "52") (pinfunction "PC11_52") (pintype "bidirectional"))
      (node (ref "TB2") (pin "21") (pinfunction "AIN1_21") (pintype "input"))
    )
    (net (code "24") (name "/D12") (class "Default")
      (node (ref "STM32") (pin "53") (pinfunction "PC12_53") (pintype "bidirectional"))
      (node (ref "TB2") (pin "17") (pinfunction "BIN1_17") (pintype "input"))
    )
    (net (code "25") (name "/D13") (class "Default")
      (node (ref "STM32") (pin "2") (pinfunction "PC13/RTC_OUT_2") (pintype "bidirectional"))
      (node (ref "TB4") (pin "16") (pinfunction "BIN2_16") (pintype "input"))
    )
    (net (code "26") (name "/D14") (class "Default")
      (node (ref "STM32") (pin "3") (pinfunction "PC14/OSC32_IN_3") (pintype "bidirectional"))
      (node (ref "TB4") (pin "17") (pinfunction "BIN1_17") (pintype "input"))
    )
    (net (code "27") (name "/D15") (class "Default")
      (node (ref "STM32") (pin "4") (pinfunction "PC15/OSC32_OUT_4") (pintype "bidirectional"))
      (node (ref "TB4") (pin "21") (pinfunction "AIN1_21") (pintype "input"))
    )
    (net (code "28") (name "/D16") (class "Default")
      (node (ref "STM32") (pin "54") (pinfunction "PD2_54") (pintype "bidirectional"))
      (node (ref "TB2") (pin "16") (pinfunction "BIN2_16") (pintype "input"))
      (node (ref "TB4") (pin "22") (pinfunction "AIN2_22") (pintype "input"))
    )
    (net (code "29") (name "/PW_2") (class "Default")
      (node (ref "STM32") (pin "56") (pinfunction "PB4_56") (pintype "bidirectional"))
    )
    (net (code "30") (name "/PW_3") (class "Default")
      (node (ref "STM32") (pin "16") (pinfunction "PA2/USART2_TX_16") (pintype "bidirectional"))
      (node (ref "TB1") (pin "15") (pinfunction "PWMB_15") (pintype "input"))
    )
    (net (code "31") (name "/PW_4") (class "Default")
      (node (ref "STM32") (pin "17") (pinfunction "PA3/USART2_RX_17") (pintype "bidirectional"))
      (node (ref "TB1") (pin "23") (pinfunction "PWMA_23") (pintype "input"))
    )
    (net (code "32") (name "/PW_5") (class "Default")
      (node (ref "STM32") (pin "55") (pinfunction "PB3_55") (pintype "bidirectional"))
      (node (ref "TB2") (pin "15") (pinfunction "PWMB_15") (pintype "input"))
    )
    (net (code "33") (name "/PW_6") (class "Default")
      (node (ref "STM32") (pin "57") (pinfunction "PB5_57") (pintype "bidirectional"))
      (node (ref "TB4") (pin "15") (pinfunction "PWMB_15") (pintype "input"))
    )
    (net (code "34") (name "/PW_7") (class "Default")
      (node (ref "STM32") (pin "15") (pinfunction "PA1/USART2_RTS_15") (pintype "bidirectional"))
      (node (ref "TB2") (pin "23") (pinfunction "PWMA_23") (pintype "input"))
      (node (ref "TB4") (pin "23") (pinfunction "PWMA_23") (pintype "input"))
    )
    (net (code "35") (name "/PW_10") (class "Default")
      (node (ref "STM32") (pin "35") (pinfunction "PB14_35") (pintype "bidirectional"))
      (node (ref "TB3") (pin "23") (pinfunction "PWMA_23") (pintype "input"))
    )
    (net (code "36") (name "/PW_20") (class "Default")
      (node (ref "STM32") (pin "36") (pinfunction "PB15_36") (pintype "bidirectional"))
      (node (ref "TB3") (pin "15") (pinfunction "PWMB_15") (pintype "input"))
    )
    (net (code "37") (name "/SWCLK") (class "Default")
      (node (ref "J23") (pin "2") (pinfunction "2_2") (pintype "passive"))
      (node (ref "STM32") (pin "49") (pinfunction "PA14/JTCK-SWCLK_49") (pintype "bidirectional"))
    )
    (net (code "38") (name "/SWDIO") (class "Default")
      (node (ref "J23") (pin "1") (pinfunction "1_1") (pintype "passive"))
      (node (ref "STM32") (pin "46") (pinfunction "PA13/JMS-SWDIO_46") (pintype "bidirectional"))
    )
    (net (code "39") (name "/USB_OTG_ID") (class "Default")
      (node (ref "STM32") (pin "43") (pinfunction "PA10_43") (pintype "bidirectional"))
      (node (ref "USB") (pin "4") (pinfunction "4_4") (pintype "input"))
    )
    (net (code "40") (name "CAN_RX1") (class "Default")
      (node (ref "SN65") (pin "4") (pinfunction "RXD_4") (pintype "output"))
      (node (ref "STM32") (pin "61") (pinfunction "PB8_61") (pintype "bidirectional"))
    )
    (net (code "41") (name "CAN_TX1") (class "Default")
      (node (ref "SN65") (pin "1") (pinfunction "TXD_1") (pintype "bidirectional"))
      (node (ref "STM32") (pin "62") (pinfunction "PB9_62") (pintype "bidirectional"))
    )
    (net (code "42") (name "CURRENT_1") (class "Default")
      (node (ref "C10") (pin "1") (pinfunction "1_1") (pintype "passive"))
      (node (ref "LM358*") (pin "7") (pinfunction "OUT1_7") (pintype "output"))
      (node (ref "R12") (pin "1") (pinfunction "1_1") (pintype "passive"))
      (node (ref "STM32") (pin "8") (pinfunction "PC0_8") (pintype "bidirectional"))
    )
    (net (code "43") (name "CURRENT_2") (class "Default")
      (node (ref "C1") (pin "1") (pinfunction "1_1") (pintype "passive"))
      (node (ref "LM358*") (pin "1") (pinfunction "OUT_1") (pintype "output"))
      (node (ref "R26") (pin "1") (pinfunction "1_1") (pintype "passive"))
      (node (ref "STM32") (pin "9") (pinfunction "PC1_9") (pintype "bidirectional"))
    )
    (net (code "44") (name "CURRENT_3") (class "Default")
      (node (ref "C12") (pin "1") (pinfunction "1_1") (pintype "passive"))
      (node (ref "LM358") (pin "7") (pinfunction "OUT1_7") (pintype "output"))
      (node (ref "R29") (pin "1") (pinfunction "1_1") (pintype "passive"))
      (node (ref "STM32") (pin "21") (pinfunction "PA5/SPI1_SCK_21") (pintype "bidirectional"))
    )
    (net (code "45") (name "CURRENT_4") (class "Default")
      (node (ref "C8") (pin "1") (pinfunction "1_1") (pintype "passive"))
      (node (ref "LM358") (pin "1") (pinfunction "OUT_1") (pintype "output"))
      (node (ref "R32") (pin "1") (pinfunction "1_1") (pintype "passive"))
      (node (ref "STM32") (pin "20") (pinfunction "PA4/USART2_CK_20") (pintype "bidirectional"))
    )
    (net (code "46") (name "D+") (class "Default")
      (node (ref "BLC") (pin "6") (pinfunction "I/O1_2_6") (pintype "bidirectional"))
      (node (ref "J2") (pin "1") (pinfunction "1_1") (pintype "passive"))
      (node (ref "USB") (pin "3") (pinfunction "3_3") (pintype "input"))
    )
    (net (code "47") (name "D-") (class "Default")
      (node (ref "BLC") (pin "4") (pinfunction "I/O2_2_4") (pintype "bidirectional"))
      (node (ref "J1") (pin "2") (pinfunction "2_2") (pintype "passive"))
      (node (ref "USB") (pin "2") (pinfunction "2_2") (pintype "input"))
    )
    (net (code "48") (name "DATA0") (class "Default")
      (node (ref "ADS") (pin "4") (pinfunction "AIN0_4") (pintype "bidirectional"))
      (node (ref "TLE4945L3") (pin "3") (pinfunction "3_3") (pintype "passive"))
    )
    (net (code "49") (name "DATA1") (class "Default")
      (node (ref "ADS") (pin "5") (pinfunction "AIN1_5") (pintype "bidirectional"))
      (node (ref "TLE4945L10") (pin "3") (pinfunction "3_3") (pintype "passive"))
    )
    (net (code "50") (name "DATA2") (class "Default")
      (node (ref "ADS") (pin "6") (pinfunction "AIN2_6") (pintype "bidirectional"))
      (node (ref "TLE4945L2") (pin "3") (pinfunction "3_3") (pintype "passive"))
    )
    (net (code "51") (name "DATA3") (class "Default")
      (node (ref "ADS") (pin "7") (pinfunction "AIN3_7") (pintype "bidirectional"))
      (node (ref "TLE4945L1") (pin "3") (pinfunction "3_3") (pintype "passive"))
    )
    (net (code "52") (name "DATA4") (class "Default")
      (node (ref "ADS1") (pin "4") (pinfunction "AIN0_4") (pintype "bidirectional"))
      (node (ref "TLE4945L7") (pin "3") (pinfunction "3_3") (pintype "passive"))
    )
    (net (code "53") (name "DATA5") (class "Default")
      (node (ref "ADS1") (pin "5") (pinfunction "AIN1_5") (pintype "bidirectional"))
      (node (ref "TLE4945L4") (pin "3") (pinfunction "3_3") (pintype "passive"))
    )
    (net (code "54") (name "DATA6") (class "Default")
      (node (ref "ADS1") (pin "6") (pinfunction "AIN2_6") (pintype "bidirectional"))
      (node (ref "TLE4945L6") (pin "3") (pinfunction "3_3") (pintype "passive"))
    )
    (net (code "55") (name "DATA7") (class "Default")
      (node (ref "ADS1") (pin "7") (pinfunction "AIN3_7") (pintype "bidirectional"))
      (node (ref "TLE4945L5") (pin "3") (pinfunction "3_3") (pintype "passive"))
    )
    (net (code "56") (name "DATA8") (class "Default")
      (node (ref "ADS2") (pin "4") (pinfunction "AIN0_4") (pintype "bidirectional"))
      (node (ref "TLE4945L8") (pin "3") (pinfunction "3_3") (pintype "passive"))
    )
    (net (code "57") (name "DATA9") (class "Default")
      (node (ref "ADS2") (pin "5") (pinfunction "AIN1_5") (pintype "bidirectional"))
      (node (ref "TLE4945L12") (pin "3") (pinfunction "3_3") (pintype "passive"))
    )
    (net (code "58") (name "DATA10") (class "Default")
      (node (ref "ADS2") (pin "6") (pinfunction "AIN2_6") (pintype "bidirectional"))
      (node (ref "TLE4945L11") (pin "3") (pinfunction "3_3") (pintype "passive"))
    )
    (net (code "59") (name "DATA11") (class "Default")
      (node (ref "ADS2") (pin "7") (pinfunction "AIN3_7") (pintype "bidirectional"))
      (node (ref "TLE4945L9") (pin "3") (pinfunction "3_3") (pintype "passive"))
    )
    (net (code "60") (name "DATA12") (class "Default")
      (node (ref "ADS3") (pin "4") (pinfunction "AIN0_4") (pintype "bidirectional"))
      (node (ref "TLE4945L16") (pin "3") (pinfunction "3_3") (pintype "passive"))
    )
    (net (code "61") (name "DATA13") (class "Default")
      (node (ref "ADS3") (pin "5") (pinfunction "AIN1_5") (pintype "bidirectional"))
      (node (ref "TLE4945L13") (pin "3") (pinfunction "3_3") (pintype "passive"))
    )
    (net (code "62") (name "DATA14") (class "Default")
      (node (ref "ADS3") (pin "6") (pinfunction "AIN2_6") (pintype "bidirectional"))
      (node (ref "TLE4945L15") (pin "3") (pinfunction "3_3") (pintype "passive"))
    )
    (net (code "63") (name "DATA15") (class "Default")
      (node (ref "ADS3") (pin "7") (pinfunction "AIN3_7") (pintype "bidirectional"))
      (node (ref "TLE4945L14") (pin "3") (pinfunction "3_3") (pintype "passive"))
    )
    (net (code "64") (name "GND") (class "Default")
      (node (ref "ADS") (pin "3") (pinfunction "VSS_3") (pintype "bidirectional"))
      (node (ref "ADS1") (pin "3") (pinfunction "VSS_3") (pintype "bidirectional"))
      (node (ref "ADS2") (pin "1") (pinfunction "ADDR_1") (pintype "bidirectional"))
      (node (ref "ADS2") (pin "3") (pinfunction "VSS_3") (pintype "bidirectional"))
      (node (ref "ADS3") (pin "1") (pinfunction "ADDR_1") (pintype "bidirectional"))
      (node (ref "ADS3") (pin "3") (pinfunction "VSS_3") (pintype "bidirectional"))
      (node (ref "AMS_3") (pin "1") (pinfunction "ADJ/GND_1") (pintype "power_in"))
      (node (ref "AMS_5") (pin "1") (pinfunction "ADJ/GND_1") (pintype "power_in"))
      (node (ref "BLC") (pin "2") (pinfunction "GND_2") (pintype "power_in"))
      (node (ref "C1") (pin "2") (pinfunction "2_2") (pintype "passive"))
      (node (ref "C10") (pin "2") (pinfunction "2_2") (pintype "passive"))
      (node (ref "C11") (pin "-") (pinfunction "-_-") (pintype "passive"))
      (node (ref "C12") (pin "2") (pinfunction "2_2") (pintype "passive"))
      (node (ref "C13") (pin "-") (pinfunction "-_-") (pintype "passive"))
      (node (ref "C15") (pin "2") (pinfunction "2_2") (pintype "passive"))
      (node (ref "C16") (pin "2") (pinfunction "2_2") (pintype "passive"))
      (node (ref "C17") (pin "2") (pinfunction "2_2") (pintype "passive"))
      (node (ref "C18") (pin "2") (pinfunction "2_2") (pintype "passive"))
      (node (ref "C19") (pin "2") (pinfunction "2_2") (pintype "passive"))
      (node (ref "C2") (pin "2") (pinfunction "2_2") (pintype "passive"))
      (node (ref "C20") (pin "2") (pinfunction "2_2") (pintype "passive"))
      (node (ref "C21") (pin "2") (pinfunction "2_2") (pintype "passive"))
      (node (ref "C22") (pin "2") (pinfunction "2_2") (pintype "passive"))
      (node (ref "C23") (pin "2") (pinfunction "2_2") (pintype "passive"))
      (node (ref "C26") (pin "2") (pinfunction "2_2") (pintype "passive"))
      (node (ref "C27") (pin "2") (pinfunction "2_2") (pintype "passive"))
      (node (ref "C28") (pin "1") (pinfunction "1_1") (pintype "passive"))
      (node (ref "C3") (pin "2") (pinfunction "2_2") (pintype "passive"))
      (node (ref "C31") (pin "1") (pinfunction "1_1") (pintype "passive"))
      (node (ref "C33") (pin "2") (pinfunction "2_2") (pintype "passive"))
      (node (ref "C35") (pin "2") (pinfunction "2_2") (pintype "passive"))
      (node (ref "C36") (pin "-") (pinfunction "-_-") (pintype "passive"))
      (node (ref "C37") (pin "-") (pinfunction "-_-") (pintype "passive"))
      (node (ref "C38") (pin "1") (pinfunction "1_1") (pintype "passive"))
      (node (ref "C4") (pin "1") (pinfunction "1_1") (pintype "passive"))
      (node (ref "C5") (pin "1") (pinfunction "1_1") (pintype "passive"))
      (node (ref "C6") (pin "1") (pinfunction "1_1") (pintype "passive"))
      (node (ref "C7") (pin "-") (pinfunction "-_-") (pintype "passive"))
      (node (ref "C8") (pin "2") (pinfunction "2_2") (pintype "passive"))
      (node (ref "C9") (pin "-") (pinfunction "-_-") (pintype "passive"))
      (node (ref "DIOD") (pin "A") (pinfunction "1_A") (pintype "bidirectional"))
      (node (ref "J2") (pin "2") (pinfunction "2_2") (pintype "passive"))
      (node (ref "J25") (pin "2") (pinfunction "2_2") (pintype "passive"))
      (node (ref "J29") (pin "2") (pinfunction "2_2") (pintype "passive"))
      (node (ref "J31") (pin "2") (pinfunction "2_2") (pintype "passive"))
      (node (ref "J33") (pin "2") (pinfunction "2_2") (pintype "passive"))
      (node (ref "J35") (pin "2") (pinfunction "2_2") (pintype "passive"))
      (node (ref "J37") (pin "2") (pinfunction "2_2") (pintype "passive"))
      (node (ref "J39") (pin "2") (pinfunction "2_2") (pintype "passive"))
      (node (ref "LM358") (pin "4") (pinfunction "V-_4") (pintype "power_in"))
      (node (ref "LM358*") (pin "4") (pinfunction "V-_4") (pintype "power_in"))
      (node (ref "R1") (pin "2") (pinfunction "2_2") (pintype "passive"))
      (node (ref "R2") (pin "2") (pinfunction "2_2") (pintype "passive"))
      (node (ref "R25") (pin "1") (pinfunction "1_1") (pintype "passive"))
      (node (ref "R28") (pin "1") (pinfunction "1_1") (pintype "passive"))
      (node (ref "R3") (pin "2") (pinfunction "2_2") (pintype "passive"))
      (node (ref "R31") (pin "1") (pinfunction "1_1") (pintype "passive"))
      (node (ref "R34") (pin "1") (pinfunction "1_1") (pintype "passive"))
      (node (ref "R4") (pin "2") (pinfunction "2_2") (pintype "passive"))
      (node (ref "R5") (pin "1") (pinfunction "1_1") (pintype "passive"))
      (node (ref "R6") (pin "2") (pinfunction "2_2") (pintype "passive"))
      (node (ref "SN65") (pin "2") (pinfunction "GND_2") (pintype "power_in"))
      (node (ref "SN65") (pin "8") (pinfunction "RS_8") (pintype "input"))
      (node (ref "STM32") (pin "12") (pinfunction "VSSA_12") (pintype "power_in"))
      (node (ref "STM32") (pin "18") (pinfunction "VSS_18") (pintype "power_in"))
      (node (ref "STM32") (pin "60") (pinfunction "BOOT0_60") (pintype "bidirectional"))
      (node (ref "STM32") (pin "63") (pinfunction "VSS_63") (pintype "power_in"))
      (node (ref "TLE4945L1") (pin "1") (pinfunction "1_1") (pintype "passive"))
      (node (ref "TLE4945L10") (pin "1") (pinfunction "1_1") (pintype "passive"))
      (node (ref "TLE4945L11") (pin "1") (pinfunction "1_1") (pintype "passive"))
      (node (ref "TLE4945L12") (pin "1") (pinfunction "1_1") (pintype "passive"))
      (node (ref "TLE4945L13") (pin "1") (pinfunction "1_1") (pintype "passive"))
      (node (ref "TLE4945L14") (pin "1") (pinfunction "1_1") (pintype "passive"))
      (node (ref "TLE4945L15") (pin "1") (pinfunction "1_1") (pintype "passive"))
      (node (ref "TLE4945L16") (pin "1") (pinfunction "1_1") (pintype "passive"))
      (node (ref "TLE4945L17") (pin "3") (pinfunction "3_3") (pintype "passive"))
      (node (ref "TLE4945L18") (pin "3") (pinfunction "3_3") (pintype "passive"))
      (node (ref "TLE4945L19") (pin "3") (pinfunction "3_3") (pintype "passive"))
      (node (ref "TLE4945L2") (pin "1") (pinfunction "1_1") (pintype "passive"))
      (node (ref "TLE4945L20") (pin "3") (pinfunction "3_3") (pintype "passive"))
      (node (ref "TLE4945L21") (pin "3") (pinfunction "3_3") (pintype "passive"))
      (node (ref "TLE4945L22") (pin "3") (pinfunction "3_3") (pintype "passive"))
      (node (ref "TLE4945L23") (pin "3") (pinfunction "3_3") (pintype "passive"))
      (node (ref "TLE4945L24") (pin "3") (pinfunction "3_3") (pintype "passive"))
      (node (ref "TLE4945L3") (pin "1") (pinfunction "1_1") (pintype "passive"))
      (node (ref "TLE4945L4") (pin "1") (pinfunction "1_1") (pintype "passive"))
      (node (ref "TLE4945L5") (pin "1") (pinfunction "1_1") (pintype "passive"))
      (node (ref "TLE4945L6") (pin "1") (pinfunction "1_1") (pintype "passive"))
      (node (ref "TLE4945L7") (pin "1") (pinfunction "1_1") (pintype "passive"))
      (node (ref "TLE4945L8") (pin "1") (pinfunction "1_1") (pintype "passive"))
      (node (ref "TLE4945L9") (pin "1") (pinfunction "1_1") (pintype "passive"))
      (node (ref "USB") (pin "5") (pinfunction "5_5") (pintype "input"))
      (node (ref "USB") (pin "M1") (pinfunction "GND1_M1") (pintype "bidirectional"))
      (node (ref "USB") (pin "M2") (pinfunction "GND2_M2") (pintype "bidirectional"))
      (node (ref "USB") (pin "M3") (pinfunction "GND3_M3") (pintype "bidirectional"))
      (node (ref "USB") (pin "M4") (pinfunction "GND4_M4") (pintype "bidirectional"))
      (node (ref "X9") (pin "1") (pinfunction "KL_1") (pintype "passive"))
      (node (ref "XL4015") (pin "1") (pinfunction "GND_1") (pintype "bidirectional"))
    )
    (net (code "65") (name "MOTOR_1") (class "Default")
      (node (ref "LM358*") (pin "3") (pinfunction "+IN_3") (pintype "input"))
      (node (ref "R28") (pin "2") (pinfunction "2_2") (pintype "passive"))
      (node (ref "TB4") (pin "10") (pinfunction "PGND2_10") (pintype "passive"))
      (node (ref "TB4") (pin "18") (pinfunction "GND_18") (pintype "passive"))
      (node (ref "TB4") (pin "3") (pinfunction "PGND1_3") (pintype "passive"))
      (node (ref "TB4") (pin "4") (pinfunction "PGND1_4") (pintype "passive"))
      (node (ref "TB4") (pin "9") (pinfunction "PGND2_9") (pintype "passive"))
    )
    (net (code "66") (name "MOTOR_2") (class "Default")
      (node (ref "LM358") (pin "5") (pinfunction "+IN1_5") (pintype "input"))
      (node (ref "R31") (pin "2") (pinfunction "2_2") (pintype "passive"))
      (node (ref "TB1") (pin "10") (pinfunction "PGND2_10") (pintype "passive"))
      (node (ref "TB1") (pin "18") (pinfunction "GND_18") (pintype "passive"))
      (node (ref "TB1") (pin "3") (pinfunction "PGND1_3") (pintype "passive"))
      (node (ref "TB1") (pin "4") (pinfunction "PGND1_4") (pintype "passive"))
      (node (ref "TB1") (pin "9") (pinfunction "PGND2_9") (pintype "passive"))
    )
    (net (code "67") (name "MOTOR_3") (class "Default")
      (node (ref "LM358*") (pin "5") (pinfunction "+IN1_5") (pintype "input"))
      (node (ref "R25") (pin "2") (pinfunction "2_2") (pintype "passive"))
      (node (ref "TB2") (pin "10") (pinfunction "PGND2_10") (pintype "passive"))
      (node (ref "TB2") (pin "18") (pinfunction "GND_18") (pintype "passive"))
      (node (ref "TB2") (pin "3") (pinfunction "PGND1_3") (pintype "passive"))
      (node (ref "TB2") (pin "4") (pinfunction "PGND1_4") (pintype "passive"))
      (node (ref "TB2") (pin "9") (pinfunction "PGND2_9") (pintype "passive"))
    )
    (net (code "68") (name "MOTOR_4") (class "Default")
      (node (ref "LM358") (pin "3") (pinfunction "+IN_3") (pintype "input"))
      (node (ref "R34") (pin "2") (pinfunction "2_2") (pintype "passive"))
      (node (ref "TB3") (pin "10") (pinfunction "PGND2_10") (pintype "passive"))
      (node (ref "TB3") (pin "18") (pinfunction "GND_18") (pintype "passive"))
      (node (ref "TB3") (pin "3") (pinfunction "PGND1_3") (pintype "passive"))
      (node (ref "TB3") (pin "4") (pinfunction "PGND1_4") (pintype "passive"))
      (node (ref "TB3") (pin "9") (pinfunction "PGND2_9") (pintype "passive"))
    )
    (net (code "69") (name "Net-(BLC-I{slash}O1_1)") (class "Default")
      (node (ref "BLC") (pin "1") (pinfunction "I/O1_1_1") (pintype "bidirectional"))
      (node (ref "R23") (pin "1") (pinfunction "1_1") (pintype "passive"))
    )
    (net (code "70") (name "Net-(BLC-I{slash}O2_1)") (class "Default")
      (node (ref "BLC") (pin "3") (pinfunction "I/O2_1_3") (pintype "bidirectional"))
      (node (ref "R24") (pin "1") (pinfunction "1_1") (pintype "passive"))
    )
    (net (code "71") (name "Net-(CR-2)") (class "Default")
      (node (ref "C19") (pin "1") (pinfunction "1_1") (pintype "passive"))
      (node (ref "CR") (pin "3") (pinfunction "2_3") (pintype "passive"))
      (node (ref "STM32") (pin "5") (pinfunction "PH0/OSC_IN_5") (pintype "bidirectional"))
    )
    (net (code "72") (name "Net-(D1-PadA)") (class "Default")
      (node (ref "D1") (pin "A") (pinfunction "A_A") (pintype "passive"))
      (node (ref "J1") (pin "1") (pinfunction "1_1") (pintype "passive"))
      (node (ref "USB") (pin "1") (pinfunction "1_1") (pintype "input"))
    )
    (net (code "73") (name "Net-(DIOD-2)") (class "Default")
      (node (ref "DIOD") (pin "C") (pinfunction "2_C") (pintype "bidirectional"))
      (node (ref "L2") (pin "1") (pinfunction "1_1") (pintype "passive"))
      (node (ref "XL4015") (pin "3") (pinfunction "SW_3") (pintype "bidirectional"))
      (node (ref "XL4015") (pin "6") (pinfunction "SW_1_6") (pintype "bidirectional"))
    )
    (net (code "74") (name "Net-(J29-Pad1)") (class "Default")
      (node (ref "J29") (pin "1") (pinfunction "1_1") (pintype "passive"))
      (node (ref "J37") (pin "1") (pinfunction "1_1") (pintype "passive"))
      (node (ref "J39") (pin "1") (pinfunction "1_1") (pintype "passive"))
      (node (ref "R40") (pin "2") (pinfunction "2_2") (pintype "passive"))
      (node (ref "R43") (pin "2") (pinfunction "2_2") (pintype "passive"))
    )
    (net (code "75") (name "Net-(J31-Pad1)") (class "Default")
      (node (ref "J31") (pin "1") (pinfunction "1_1") (pintype "passive"))
      (node (ref "J33") (pin "1") (pinfunction "1_1") (pintype "passive"))
      (node (ref "J35") (pin "1") (pinfunction "1_1") (pintype "passive"))
      (node (ref "R41") (pin "2") (pinfunction "2_2") (pintype "passive"))
      (node (ref "R42") (pin "2") (pinfunction "2_2") (pintype "passive"))
    )
    (net (code "76") (name "Net-(LED2-PadC)") (class "Default")
      (node (ref "LED2") (pin "C") (pinfunction "C_C") (pintype "passive"))
      (node (ref "R1") (pin "1") (pinfunction "1_1") (pintype "passive"))
    )
    (net (code "77") (name "Net-(LM358*--IN)") (class "Default")
      (node (ref "LM358*") (pin "2") (pinfunction "-IN_2") (pintype "input"))
      (node (ref "R26") (pin "2") (pinfunction "2_2") (pintype "passive"))
      (node (ref "R6") (pin "1") (pinfunction "1_1") (pintype "passive"))
    )
    (net (code "78") (name "Net-(LM358*--IN1)") (class "Default")
      (node (ref "LM358*") (pin "6") (pinfunction "-IN1_6") (pintype "input"))
      (node (ref "R12") (pin "2") (pinfunction "2_2") (pintype "passive"))
      (node (ref "R4") (pin "1") (pinfunction "1_1") (pintype "passive"))
    )
    (net (code "79") (name "Net-(LM358--IN)") (class "Default")
      (node (ref "LM358") (pin "2") (pinfunction "-IN_2") (pintype "input"))
      (node (ref "R3") (pin "1") (pinfunction "1_1") (pintype "passive"))
      (node (ref "R32") (pin "2") (pinfunction "2_2") (pintype "passive"))
    )
    (net (code "80") (name "Net-(LM358--IN1)") (class "Default")
      (node (ref "LM358") (pin "6") (pinfunction "-IN1_6") (pintype "input"))
      (node (ref "R2") (pin "1") (pinfunction "1_1") (pintype "passive"))
      (node (ref "R29") (pin "2") (pinfunction "2_2") (pintype "passive"))
    )
    (net (code "81") (name "Net-(SN65-CANH)") (class "Default")
      (node (ref "J27") (pin "1") (pinfunction "1_1") (pintype "passive"))
      (node (ref "R18") (pin "1") (pinfunction "1_1") (pintype "passive"))
      (node (ref "SN65") (pin "7") (pinfunction "CANH_7") (pintype "bidirectional"))
    )
    (net (code "82") (name "Net-(SN65-CANL)") (class "Default")
      (node (ref "J27") (pin "2") (pinfunction "2_2") (pintype "passive"))
      (node (ref "R18") (pin "2") (pinfunction "2_2") (pintype "passive"))
      (node (ref "SN65") (pin "6") (pinfunction "CANL_6") (pintype "bidirectional"))
    )
    (net (code "83") (name "Net-(STM32-NRST)") (class "Default")
      (node (ref "C2") (pin "1") (pinfunction "1_1") (pintype "passive"))
      (node (ref "R13") (pin "1") (pinfunction "1_1") (pintype "passive"))
      (node (ref "STM32") (pin "7") (pinfunction "NRST_7") (pintype "bidirectional"))
    )
    (net (code "84") (name "Net-(STM32-PH1{slash}OSC_OUT)") (class "Default")
      (node (ref "C18") (pin "1") (pinfunction "1_1") (pintype "passive"))
      (node (ref "CR") (pin "1") (pinfunction "1_1") (pintype "passive"))
      (node (ref "STM32") (pin "6") (pinfunction "PH1/OSC_OUT_6") (pintype "bidirectional"))
    )
    (net (code "85") (name "Net-(STM32-VCAP_1)") (class "Default")
      (node (ref "C27") (pin "1") (pinfunction "1_1") (pintype "passive"))
      (node (ref "STM32") (pin "31") (pinfunction "VCAP_1_31") (pintype "power_in"))
    )
    (net (code "86") (name "Net-(STM32-VCAP_2)") (class "Default")
      (node (ref "C26") (pin "1") (pinfunction "1_1") (pintype "passive"))
      (node (ref "STM32") (pin "47") (pinfunction "VCAP_2_47") (pintype "power_in"))
    )
    (net (code "87") (name "Net-(X2A-KL)") (class "Default")
      (node (ref "TB3") (pin "1") (pinfunction "AO1_1") (pintype "output"))
      (node (ref "TB3") (pin "2") (pinfunction "AO1_2") (pintype "output"))
      (node (ref "X2") (pin "1") (pinfunction "KL_1") (pintype "passive"))
    )
    (net (code "88") (name "Net-(X2B-KL)") (class "Default")
      (node (ref "TB3") (pin "5") (pinfunction "AO2_5") (pintype "output"))
      (node (ref "TB3") (pin "6") (pinfunction "AO2_6") (pintype "output"))
      (node (ref "X2") (pin "2") (pinfunction "KL_2") (pintype "passive"))
    )
    (net (code "89") (name "Net-(X3A-KL)") (class "Default")
      (node (ref "TB1") (pin "7") (pinfunction "BO2_7") (pintype "output"))
      (node (ref "TB1") (pin "8") (pinfunction "BO2_8") (pintype "output"))
      (node (ref "X3") (pin "1") (pinfunction "KL_1") (pintype "passive"))
    )
    (net (code "90") (name "Net-(X3B-KL)") (class "Default")
      (node (ref "TB1") (pin "11") (pinfunction "BO1_11") (pintype "output"))
      (node (ref "TB1") (pin "12") (pinfunction "BO1_12") (pintype "output"))
      (node (ref "X3") (pin "2") (pinfunction "KL_2") (pintype "passive"))
    )
    (net (code "91") (name "Net-(X4A-KL)") (class "Default")
      (node (ref "TB1") (pin "1") (pinfunction "AO1_1") (pintype "output"))
      (node (ref "TB1") (pin "2") (pinfunction "AO1_2") (pintype "output"))
      (node (ref "X4") (pin "1") (pinfunction "KL_1") (pintype "passive"))
    )
    (net (code "92") (name "Net-(X4B-KL)") (class "Default")
      (node (ref "TB1") (pin "5") (pinfunction "AO2_5") (pintype "output"))
      (node (ref "TB1") (pin "6") (pinfunction "AO2_6") (pintype "output"))
      (node (ref "X4") (pin "2") (pinfunction "KL_2") (pintype "passive"))
    )
    (net (code "93") (name "Net-(X5A-KL)") (class "Default")
      (node (ref "TB2") (pin "7") (pinfunction "BO2_7") (pintype "output"))
      (node (ref "TB2") (pin "8") (pinfunction "BO2_8") (pintype "output"))
      (node (ref "X5") (pin "1") (pinfunction "KL_1") (pintype "passive"))
    )
    (net (code "94") (name "Net-(X5B-KL)") (class "Default")
      (node (ref "TB2") (pin "11") (pinfunction "BO1_11") (pintype "output"))
      (node (ref "TB2") (pin "12") (pinfunction "BO1_12") (pintype "output"))
      (node (ref "X5") (pin "2") (pinfunction "KL_2") (pintype "passive"))
    )
    (net (code "95") (name "Net-(X6A-KL)") (class "Default")
      (node (ref "TB2") (pin "1") (pinfunction "AO1_1") (pintype "output"))
      (node (ref "TB2") (pin "2") (pinfunction "AO1_2") (pintype "output"))
      (node (ref "X6") (pin "1") (pinfunction "KL_1") (pintype "passive"))
    )
    (net (code "96") (name "Net-(X6B-KL)") (class "Default")
      (node (ref "TB2") (pin "5") (pinfunction "AO2_5") (pintype "output"))
      (node (ref "TB2") (pin "6") (pinfunction "AO2_6") (pintype "output"))
      (node (ref "X6") (pin "2") (pinfunction "KL_2") (pintype "passive"))
    )
    (net (code "97") (name "Net-(X7A-KL)") (class "Default")
      (node (ref "TB4") (pin "7") (pinfunction "BO2_7") (pintype "output"))
      (node (ref "TB4") (pin "8") (pinfunction "BO2_8") (pintype "output"))
      (node (ref "X7") (pin "1") (pinfunction "KL_1") (pintype "passive"))
    )
    (net (code "98") (name "Net-(X7B-KL)") (class "Default")
      (node (ref "TB4") (pin "11") (pinfunction "BO1_11") (pintype "output"))
      (node (ref "TB4") (pin "12") (pinfunction "BO1_12") (pintype "output"))
      (node (ref "X7") (pin "2") (pinfunction "KL_2") (pintype "passive"))
    )
    (net (code "99") (name "Net-(X8A-KL)") (class "Default")
      (node (ref "TB4") (pin "1") (pinfunction "AO1_1") (pintype "output"))
      (node (ref "TB4") (pin "2") (pinfunction "AO1_2") (pintype "output"))
      (node (ref "X8") (pin "1") (pinfunction "KL_1") (pintype "passive"))
    )
    (net (code "100") (name "Net-(X8B-KL)") (class "Default")
      (node (ref "TB4") (pin "5") (pinfunction "AO2_5") (pintype "output"))
      (node (ref "TB4") (pin "6") (pinfunction "AO2_6") (pintype "output"))
      (node (ref "X8") (pin "2") (pinfunction "KL_2") (pintype "passive"))
    )
    (net (code "101") (name "Net-(X13A-KL)") (class "Default")
      (node (ref "TB3") (pin "7") (pinfunction "BO2_7") (pintype "output"))
      (node (ref "TB3") (pin "8") (pinfunction "BO2_8") (pintype "output"))
      (node (ref "X13") (pin "1") (pinfunction "KL_1") (pintype "passive"))
    )
    (net (code "102") (name "Net-(X13B-KL)") (class "Default")
      (node (ref "TB3") (pin "11") (pinfunction "BO1_11") (pintype "output"))
      (node (ref "TB3") (pin "12") (pinfunction "BO1_12") (pintype "output"))
      (node (ref "X13") (pin "2") (pinfunction "KL_2") (pintype "passive"))
    )
    (net (code "103") (name "Net-(XL4015-FB)") (class "Default")
      (node (ref "C34") (pin "2") (pinfunction "2_2") (pintype "passive"))
      (node (ref "R16") (pin "1") (pinfunction "1_1") (pintype "passive"))
      (node (ref "R5") (pin "2") (pinfunction "2_2") (pintype "passive"))
      (node (ref "XL4015") (pin "2") (pinfunction "FB_2") (pintype "bidirectional"))
    )
    (net (code "104") (name "Net-(XL4015-VC)") (class "Default")
      (node (ref "C32") (pin "2") (pinfunction "2_2") (pintype "passive"))
      (node (ref "XL4015") (pin "4") (pinfunction "VC_4") (pintype "bidirectional"))
    )
    (net (code "105") (name "SCL1") (class "Default")
      (node (ref "ADS1") (pin "10") (pinfunction "SCL_10") (pintype "bidirectional"))
      (node (ref "ADS3") (pin "10") (pinfunction "SCL_10") (pintype "bidirectional"))
      (node (ref "J28") (pin "1") (pinfunction "1_1") (pintype "passive"))
      (node (ref "J36") (pin "1") (pinfunction "1_1") (pintype "passive"))
      (node (ref "J38") (pin "1") (pinfunction "1_1") (pintype "passive"))
      (node (ref "R20") (pin "2") (pinfunction "2_2") (pintype "passive"))
      (node (ref "STM32") (pin "58") (pinfunction "PB6_58") (pintype "bidirectional"))
    )
    (net (code "106") (name "SCL2") (class "Default")
      (node (ref "ADS") (pin "10") (pinfunction "SCL_10") (pintype "bidirectional"))
      (node (ref "ADS2") (pin "10") (pinfunction "SCL_10") (pintype "bidirectional"))
      (node (ref "J30") (pin "1") (pinfunction "1_1") (pintype "passive"))
      (node (ref "J32") (pin "1") (pinfunction "1_1") (pintype "passive"))
      (node (ref "J34") (pin "1") (pinfunction "1_1") (pintype "passive"))
      (node (ref "R22") (pin "2") (pinfunction "2_2") (pintype "passive"))
      (node (ref "STM32") (pin "29") (pinfunction "PB10_29") (pintype "bidirectional"))
    )
    (net (code "107") (name "SDA1") (class "Default")
      (node (ref "ADS1") (pin "9") (pinfunction "SDA_9") (pintype "bidirectional"))
      (node (ref "ADS3") (pin "9") (pinfunction "SDA_9") (pintype "bidirectional"))
      (node (ref "J28") (pin "2") (pinfunction "2_2") (pintype "passive"))
      (node (ref "J36") (pin "2") (pinfunction "2_2") (pintype "passive"))
      (node (ref "J38") (pin "2") (pinfunction "2_2") (pintype "passive"))
      (node (ref "R19") (pin "2") (pinfunction "2_2") (pintype "passive"))
      (node (ref "STM32") (pin "59") (pinfunction "PB7_59") (pintype "bidirectional"))
    )
    (net (code "108") (name "SDA2") (class "Default")
      (node (ref "ADS") (pin "9") (pinfunction "SDA_9") (pintype "bidirectional"))
      (node (ref "ADS2") (pin "9") (pinfunction "SDA_9") (pintype "bidirectional"))
      (node (ref "J30") (pin "2") (pinfunction "2_2") (pintype "passive"))
      (node (ref "J32") (pin "2") (pinfunction "2_2") (pintype "passive"))
      (node (ref "J34") (pin "2") (pinfunction "2_2") (pintype "passive"))
      (node (ref "R21") (pin "2") (pinfunction "2_2") (pintype "passive"))
      (node (ref "STM32") (pin "30") (pinfunction "PB11_30") (pintype "bidirectional"))
    )
    (net (code "109") (name "USB_OTG_DM") (class "Default")
      (node (ref "R24") (pin "2") (pinfunction "2_2") (pintype "passive"))
      (node (ref "STM32") (pin "44") (pinfunction "PA11_44") (pintype "bidirectional"))
    )
    (net (code "110") (name "USB_OTG_DP") (class "Default")
      (node (ref "R23") (pin "2") (pinfunction "2_2") (pintype "passive"))
      (node (ref "STM32") (pin "45") (pinfunction "PA12_45") (pintype "bidirectional"))
    )
    (net (code "111") (name "unconnected-(ADS-ALERT{slash}RDY-Pad2)") (class "Default")
      (node (ref "ADS") (pin "2") (pinfunction "ALERT/RDY_2") (pintype "bidirectional"))
    )
    (net (code "112") (name "unconnected-(ADS1-ALERT{slash}RDY-Pad2)") (class "Default")
      (node (ref "ADS1") (pin "2") (pinfunction "ALERT/RDY_2") (pintype "bidirectional"))
    )
    (net (code "113") (name "unconnected-(ADS2-ALERT{slash}RDY-Pad2)") (class "Default")
      (node (ref "ADS2") (pin "2") (pinfunction "ALERT/RDY_2") (pintype "bidirectional"))
    )
    (net (code "114") (name "unconnected-(ADS3-ALERT{slash}RDY-Pad2)") (class "Default")
      (node (ref "ADS3") (pin "2") (pinfunction "ALERT/RDY_2") (pintype "bidirectional"))
    )
    (net (code "115") (name "unconnected-(SN65-LBK-Pad5)") (class "Default")
      (node (ref "SN65") (pin "5") (pinfunction "LBK_5") (pintype "output"))
    )
  )
)
